# Led_amp.net
KiCad netlist of a schematic drawn in EAGLE
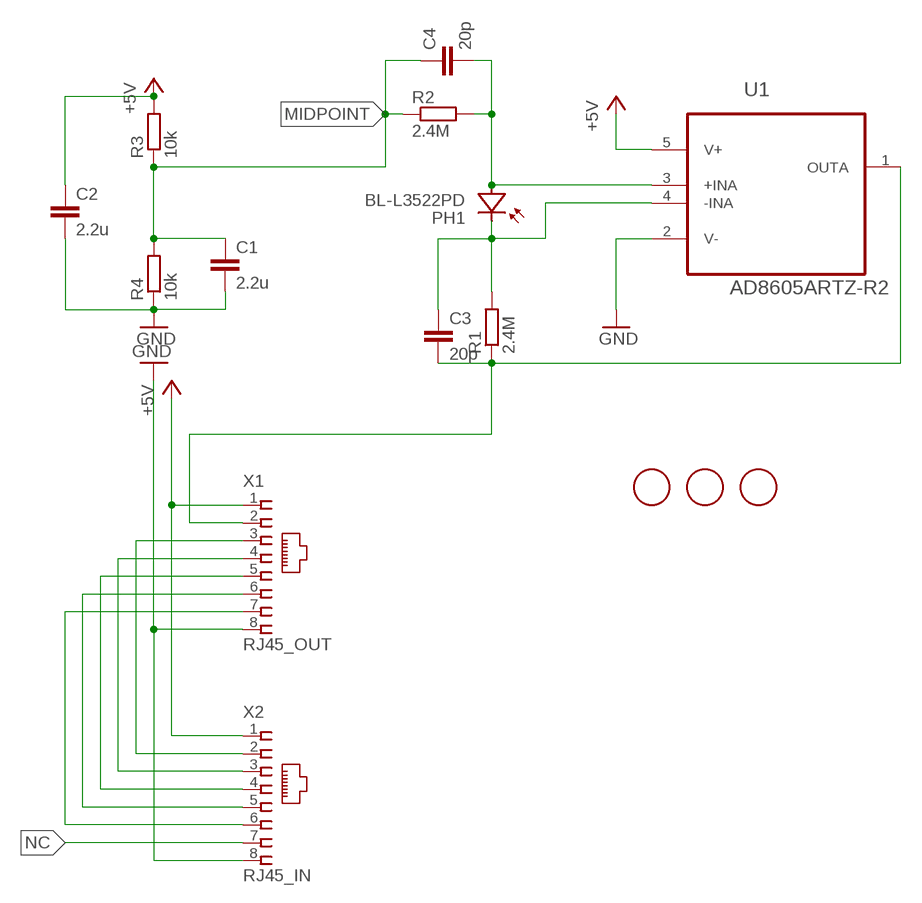
[diagram p0: schematic, sheet 1]

(export (version "E")
  (design (tool "Eeschema 10.0.6"))
  (components
    (comp (ref "C1")
      (value "2.2u")
      (footprint "eagle-import:C0805")
      (libsource (lib "eagle-import") (part "C-EUC0805"))
    )
    (comp (ref "C2")
      (value "2.2u")
      (footprint "eagle-import:C0805")
      (libsource (lib "eagle-import") (part "C-EUC0805"))
    )
    (comp (ref "C3")
      (value "20p")
      (footprint "eagle-import:C0805")
      (libsource (lib "eagle-import") (part "C-EUC0805"))
    )
    (comp (ref "C4")
      (value "20p")
      (footprint "eagle-import:C0805")
      (libsource (lib "eagle-import") (part "C-EUC0805"))
    )
    (comp (ref "PH1")
      (value "BL-L3522PD")
      (footprint "eagle-import:PDOTODIODE_RECT")
      (libsource (lib "eagle-import") (part "BL-L3522PD"))
    )
    (comp (ref "R1")
      (value "2.4M")
      (footprint "eagle-import:R0805")
      (libsource (lib "eagle-import") (part "R-EU_R0805"))
    )
    (comp (ref "R2")
      (value "2.4M")
      (footprint "eagle-import:R0805")
      (libsource (lib "eagle-import") (part "R-EU_R0805"))
    )
    (comp (ref "R3")
      (value "10k")
      (footprint "eagle-import:R0805")
      (libsource (lib "eagle-import") (part "R-EU_R0805"))
    )
    (comp (ref "R4")
      (value "10k")
      (footprint "eagle-import:R0805")
      (libsource (lib "eagle-import") (part "R-EU_R0805"))
    )
    (comp (ref "U$1")
      (value "FIDUCIALLARGE_1MM")
      (footprint "eagle-import:FIDUCIAL_1MM_LARGE")
      (libsource (lib "eagle-import") (part "FIDUCIALLARGE_1MM"))
    )
    (comp (ref "U$2")
      (value "FIDUCIALLARGE_1MM")
      (footprint "eagle-import:FIDUCIAL_1MM_LARGE")
      (libsource (lib "eagle-import") (part "FIDUCIALLARGE_1MM"))
    )
    (comp (ref "U$3")
      (value "FIDUCIALLARGE_1MM")
      (footprint "eagle-import:FIDUCIAL_1MM_LARGE")
      (libsource (lib "eagle-import") (part "FIDUCIALLARGE_1MM"))
    )
    (comp (ref "U1")
      (value "AD8605ARTZ-R2")
      (footprint "eagle-import:SOT95P290X145-5N")
      (fields (field (name "MF") "Analog Devices") (field (name "MP") "AD8605ARTZ-REEL7"))
      (libsource (lib "eagle-import") (part "AD8605ARTZ-R2"))
    )
    (comp (ref "X1")
      (value "RJ45_OUT")
      (footprint "eagle-import:DS1134")
      (libsource (lib "eagle-import") (part "RJ45DS1134"))
    )
    (comp (ref "X2")
      (value "RJ45_IN")
      (footprint "eagle-import:DS1134")
      (libsource (lib "eagle-import") (part "RJ45DS1134"))
    )
  )
  (nets
    (net (code "1") (name "+5V") (class "Default")
      (node (ref "C2") (pin "1") (pinfunction "1_1") (pintype "passive"))
      (node (ref "R3") (pin "2") (pinfunction "2_2") (pintype "passive"))
      (node (ref "U1") (pin "5") (pinfunction "V+_5") (pintype "power_in"))
      (node (ref "X1") (pin "1") (pinfunction "1_1") (pintype "passive"))
      (node (ref "X2") (pin "1") (pinfunction "1_1") (pintype "passive"))
    )
    (net (code "2") (name "GND") (class "Default")
      (node (ref "C1") (pin "2") (pinfunction "2_2") (pintype "passive"))
      (node (ref "C2") (pin "2") (pinfunction "2_2") (pintype "passive"))
      (node (ref "R4") (pin "1") (pinfunction "1_1") (pintype "passive"))
      (node (ref "U1") (pin "2") (pinfunction "V-_2") (pintype "power_in"))
      (node (ref "X1") (pin "8") (pinfunction "8_8") (pintype "passive"))
      (node (ref "X2") (pin "8") (pinfunction "8_8") (pintype "passive"))
    )
    (net (code "3") (name "MIDPOINT") (class "Default")
      (node (ref "C1") (pin "1") (pinfunction "1_1") (pintype "passive"))
      (node (ref "C4") (pin "1") (pinfunction "1_1") (pintype "passive"))
      (node (ref "R2") (pin "1") (pinfunction "1_1") (pintype "passive"))
      (node (ref "R3") (pin "1") (pinfunction "1_1") (pintype "passive"))
      (node (ref "R4") (pin "2") (pinfunction "2_2") (pintype "passive"))
    )
    (net (code "4") (name "NC") (class "Default")
      (node (ref "X2") (pin "7") (pinfunction "7_7") (pintype "passive"))
    )
    (net (code "5") (name "Net-(PH1-C)") (class "Default")
      (node (ref "C3") (pin "1") (pinfunction "1_1") (pintype "passive"))
      (node (ref "PH1") (pin "K") (pinfunction "C_K") (pintype "passive"))
      (node (ref "R1") (pin "2") (pinfunction "2_2") (pintype "passive"))
      (node (ref "U1") (pin "4") (pinfunction "-INA_4") (pintype "passive"))
    )
    (net (code "6") (name "Net-(U1-+INA)") (class "Default")
      (node (ref "C4") (pin "2") (pinfunction "2_2") (pintype "passive"))
      (node (ref "PH1") (pin "A") (pinfunction "A_A") (pintype "passive"))
      (node (ref "R2") (pin "2") (pinfunction "2_2") (pintype "passive"))
      (node (ref "U1") (pin "3") (pinfunction "+INA_3") (pintype "passive"))
    )
    (net (code "7") (name "Net-(U1-OUTA)") (class "Default")
      (node (ref "C3") (pin "2") (pinfunction "2_2") (pintype "passive"))
      (node (ref "R1") (pin "1") (pinfunction "1_1") (pintype "passive"))
      (node (ref "U1") (pin "1") (pinfunction "OUTA_1") (pintype "passive"))
      (node (ref "X1") (pin "2") (pinfunction "2_2") (pintype "passive"))
    )
    (net (code "8") (name "Net-(X1-Pad3)") (class "Default")
      (node (ref "X1") (pin "3") (pinfunction "3_3") (pintype "passive"))
      (node (ref "X2") (pin "2") (pinfunction "2_2") (pintype "passive"))
    )
    (net (code "9") (name "Net-(X1-Pad4)") (class "Default")
      (node (ref "X1") (pin "4") (pinfunction "4_4") (pintype "passive"))
      (node (ref "X2") (pin "3") (pinfunction "3_3") (pintype "passive"))
    )
    (net (code "10") (name "Net-(X1-Pad5)") (class "Default")
      (node (ref "X1") (pin "5") (pinfunction "5_5") (pintype "passive"))
      (node (ref "X2") (pin "4") (pinfunction "4_4") (pintype "passive"))
    )
    (net (code "11") (name "Net-(X1-Pad6)") (class "Default")
      (node (ref "X1") (pin "6") (pinfunction "6_6") (pintype "passive"))
      (node (ref "X2") (pin "5") (pinfunction "5_5") (pintype "passive"))
    )
    (net (code "12") (name "Net-(X1-Pad7)") (class "Default")
      (node (ref "X1") (pin "7") (pinfunction "7_7") (pintype "passive"))
      (node (ref "X2") (pin "6") (pinfunction "6_6") (pintype "passive"))
    )
  )
)
